# 08_B2B.net
KiCad netlist of a schematic drawn in Altium Designer
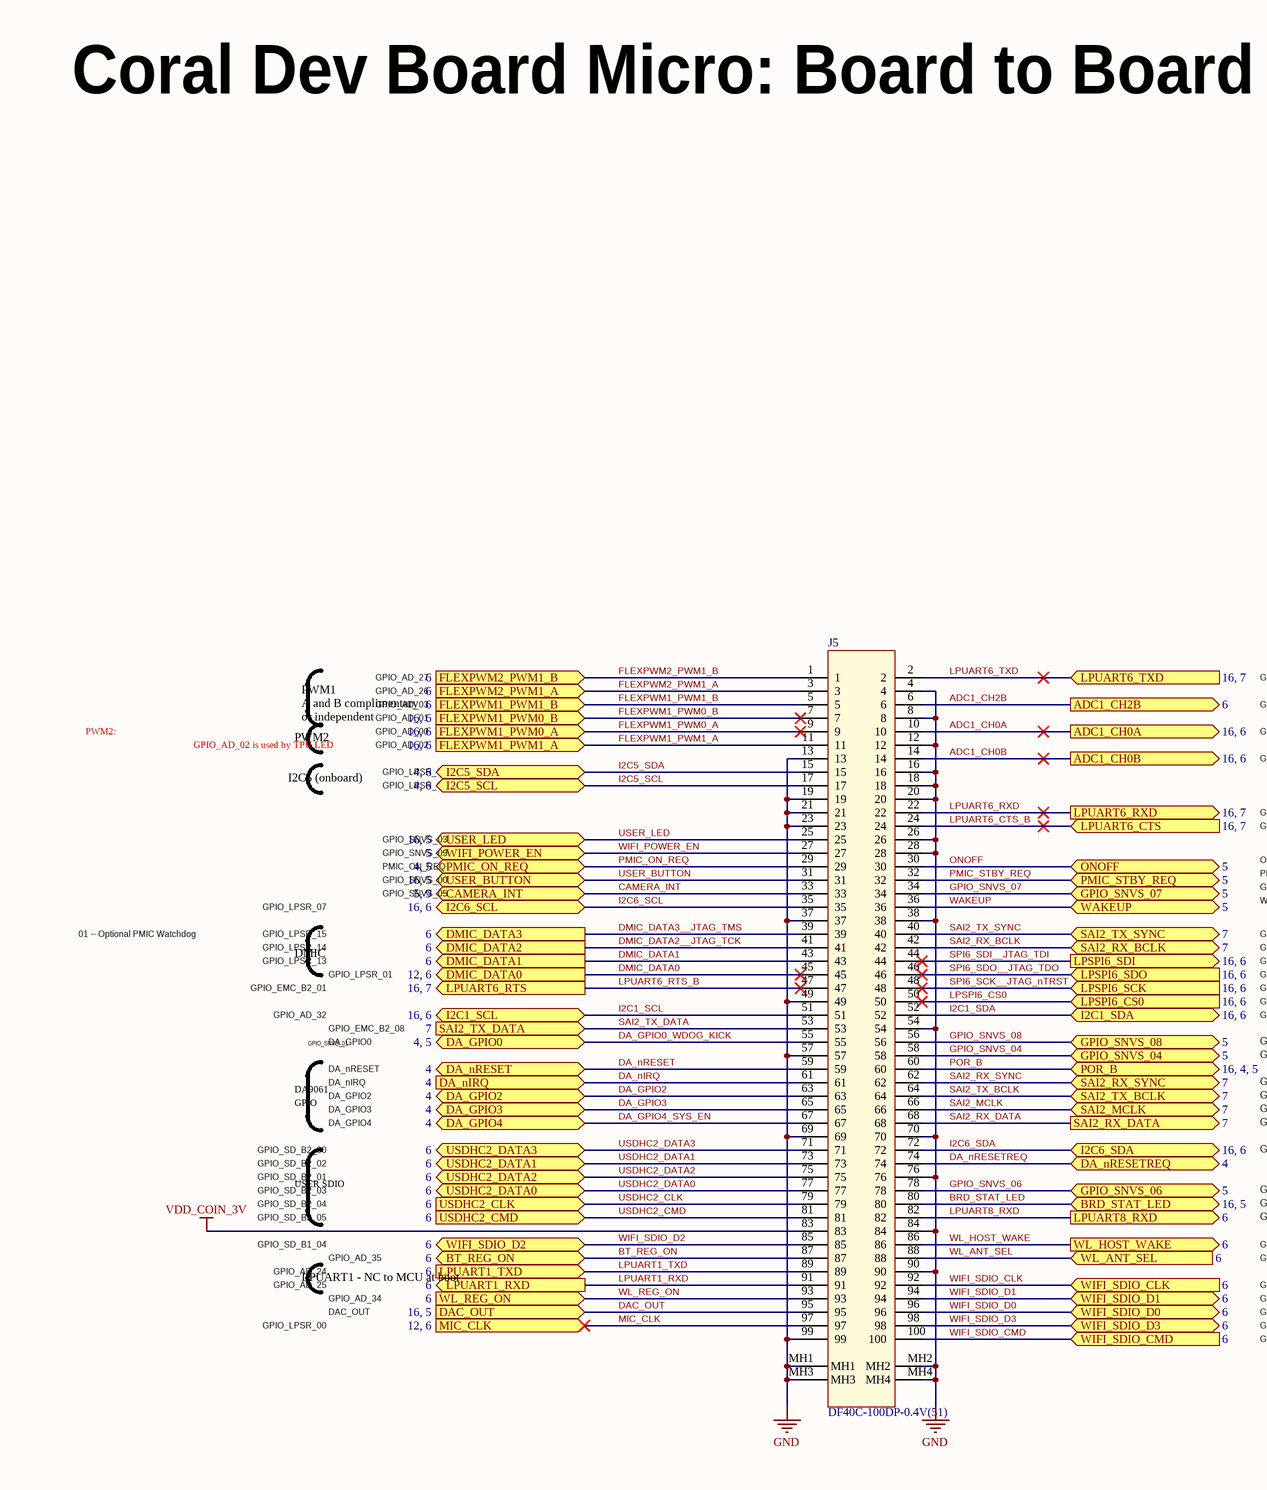
[diagram p0: 08 B2B.SchDoc, left]
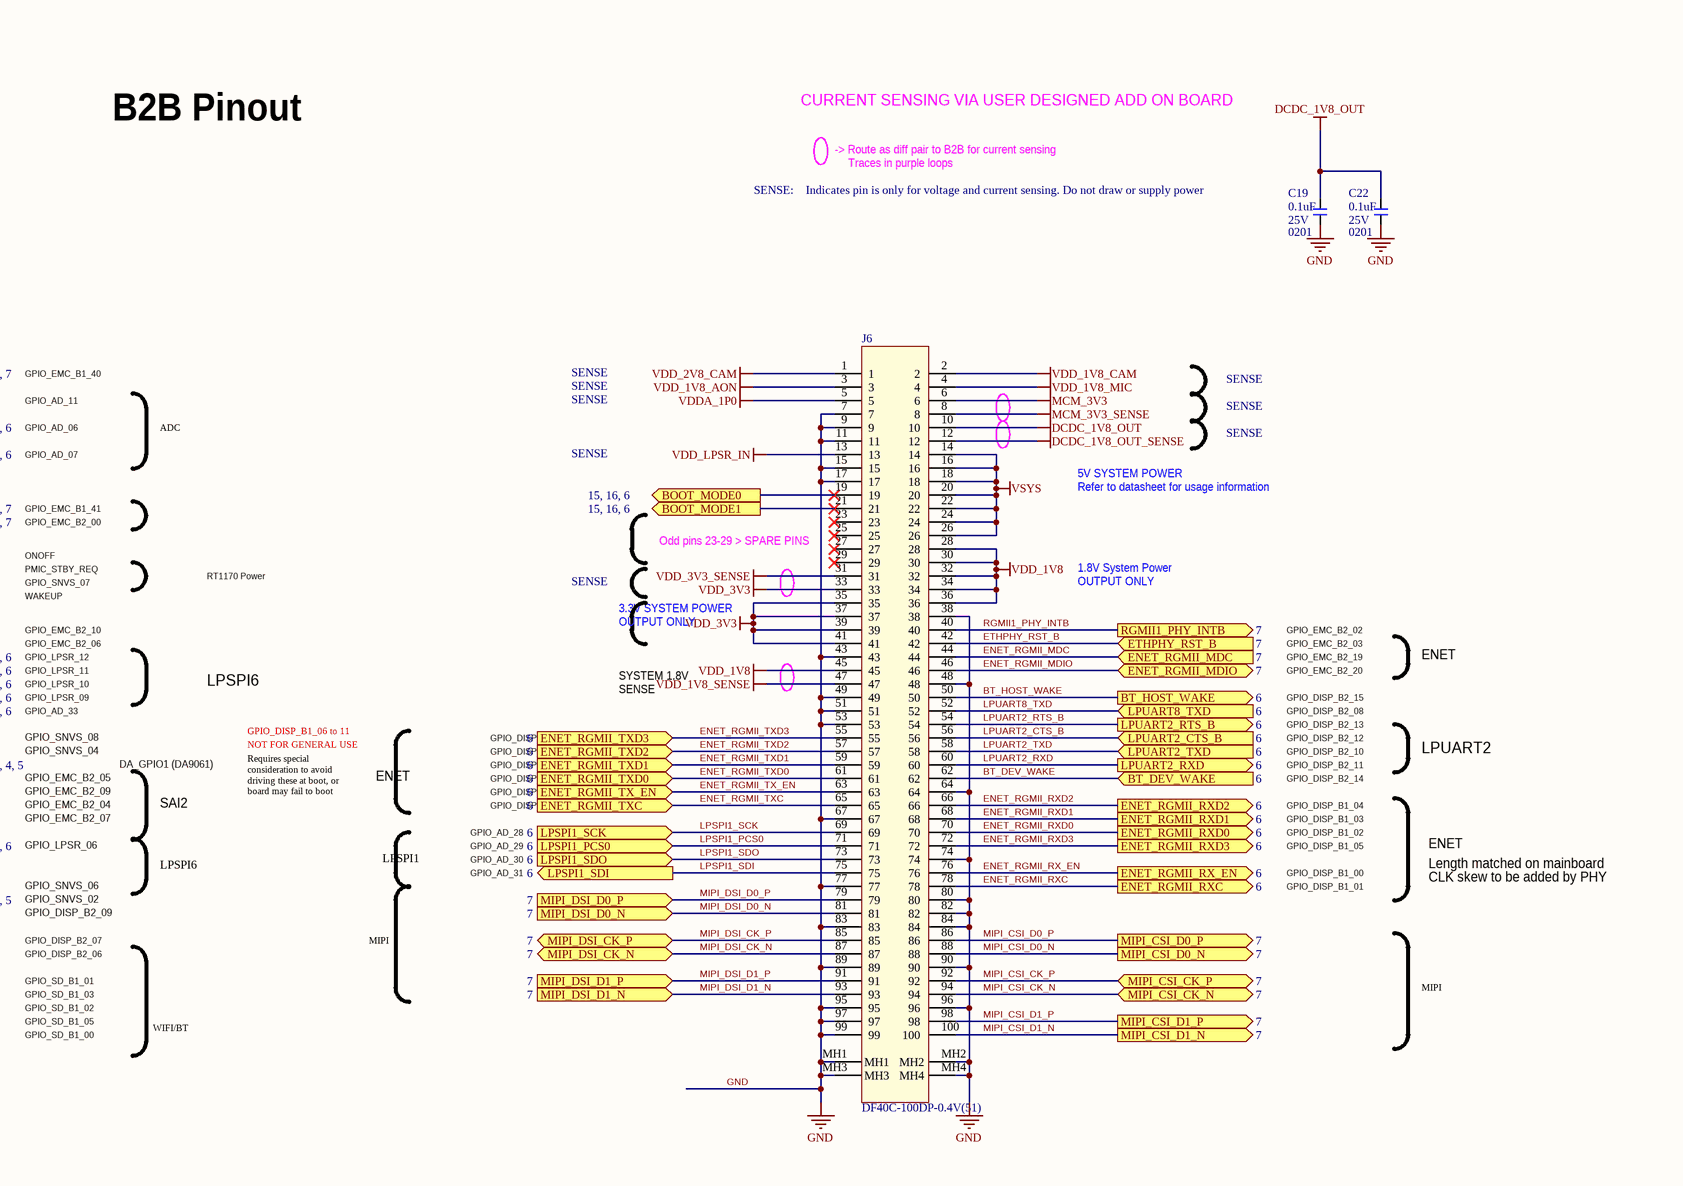
[diagram p1: 08 B2B.SchDoc, right]

(export (version "E")
  (design (tool "Eeschema 10.0.6"))
  (components
    (comp (ref "C19")
      (value "0.1uF")
      (footprint "C0201Y")
      (description "CAP, CER, X5R, 0.1uF, 25V, 20%, 0201, 0.33mm T")
      (fields
        (field (name "MFG") "MURATA")
        (field (name "PACKAGE") "0201")
        (field (name "VOLTAGE") "25V")
        (field (name "TOLERANCE") "20%")
      )
      (libsource (lib "AltiumReleaseLibDB") (part "__Template_Cap"))
    )
    (comp (ref "C22")
      (value "0.1uF")
      (footprint "C0201Y")
      (description "CAP, CER, X5R, 0.1uF, 25V, 20%, 0201, 0.33mm T")
      (fields
        (field (name "MFG") "MURATA")
        (field (name "PACKAGE") "0201")
        (field (name "VOLTAGE") "25V")
        (field (name "TOLERANCE") "20%")
      )
      (libsource (lib "AltiumReleaseLibDB") (part "__Template_Cap"))
    )
    (comp (ref "J5")
      (value "~")
      (footprint "HIROSE_DF40C-100DP-0.4V(51)")
      (description "CONN, HDR, VERT, 2x50, 0.4MM P, 1.14MM H, GOLD, SMD")
      (fields (field (name "MFG") "Hirose Electric Co Ltd") (field (name "MFG P/N") "DF40C-100DP-0.4V(51)"))
      (libsource (lib "AltiumReleaseLibDB") (part "__Template_Connector_2X50_4MH"))
    )
    (comp (ref "J6")
      (value "~")
      (footprint "HIROSE_DF40C-100DP-0.4V(51)")
      (description "CONN, HDR, VERT, 2x50, 0.4MM P, 1.14MM H, GOLD, SMD")
      (fields (field (name "MFG") "Hirose Electric Co Ltd") (field (name "MFG P/N") "DF40C-100DP-0.4V(51)"))
      (libsource (lib "AltiumReleaseLibDB") (part "__Template_Connector_2X50_4MH"))
    )
  )
  (nets
    (net (code "1") (name "/ADC1_CH0A") (class "Default")
      (node (ref "J5") (pin "10") (pinfunction "10_10") (pintype "passive"))
    )
    (net (code "2") (name "/ADC1_CH0B") (class "Default")
      (node (ref "J5") (pin "14") (pinfunction "14_14") (pintype "passive"))
    )
    (net (code "3") (name "/ADC1_CH2B") (class "Default")
      (node (ref "J5") (pin "6") (pinfunction "6_6") (pintype "passive"))
    )
    (net (code "4") (name "/BOOT_MODE0") (class "Default")
      (node (ref "J6") (pin "19") (pinfunction "19_19") (pintype "passive+no_connect"))
    )
    (net (code "5") (name "/BOOT_MODE1") (class "Default")
      (node (ref "J6") (pin "21") (pinfunction "21_21") (pintype "passive+no_connect"))
    )
    (net (code "6") (name "/BRD_STAT_LED") (class "Default")
      (node (ref "J5") (pin "80") (pinfunction "80_80") (pintype "passive"))
    )
    (net (code "7") (name "/BT_DEV_WAKE") (class "Default")
      (node (ref "J6") (pin "62") (pinfunction "62_62") (pintype "passive"))
    )
    (net (code "8") (name "/BT_HOST_WAKE") (class "Default")
      (node (ref "J6") (pin "50") (pinfunction "50_50") (pintype "passive"))
    )
    (net (code "9") (name "/BT_REG_ON") (class "Default")
      (node (ref "J5") (pin "87") (pinfunction "87_87") (pintype "passive"))
    )
    (net (code "10") (name "/CAMERA_INT") (class "Default")
      (node (ref "J5") (pin "33") (pinfunction "33_33") (pintype "passive"))
    )
    (net (code "11") (name "/DAC_OUT") (class "Default")
      (node (ref "J5") (pin "95") (pinfunction "95_95") (pintype "passive"))
    )
    (net (code "12") (name "/DA_GPIO0_WDOG_KICK") (class "Default")
      (node (ref "J5") (pin "55") (pinfunction "55_55") (pintype "passive"))
    )
    (net (code "13") (name "/DA_GPIO2") (class "Default")
      (node (ref "J5") (pin "63") (pinfunction "63_63") (pintype "passive"))
    )
    (net (code "14") (name "/DA_GPIO3") (class "Default")
      (node (ref "J5") (pin "65") (pinfunction "65_65") (pintype "passive"))
    )
    (net (code "15") (name "/DA_GPIO4_SYS_EN") (class "Default")
      (node (ref "J5") (pin "67") (pinfunction "67_67") (pintype "passive"))
    )
    (net (code "16") (name "/DA_nIRQ") (class "Default")
      (node (ref "J5") (pin "61") (pinfunction "61_61") (pintype "passive"))
    )
    (net (code "17") (name "/DA_nRESET") (class "Default")
      (node (ref "J5") (pin "59") (pinfunction "59_59") (pintype "passive"))
    )
    (net (code "18") (name "/DA_nRESETREQ") (class "Default")
      (node (ref "J5") (pin "74") (pinfunction "74_74") (pintype "passive"))
    )
    (net (code "19") (name "/DMIC_DATA0") (class "Default")
      (node (ref "J5") (pin "45") (pinfunction "45_45") (pintype "passive+no_connect"))
    )
    (net (code "20") (name "/DMIC_DATA1") (class "Default")
      (node (ref "J5") (pin "43") (pinfunction "43_43") (pintype "passive"))
    )
    (net (code "21") (name "/DMIC_DATA2__JTAG_TCK") (class "Default")
      (node (ref "J5") (pin "41") (pinfunction "41_41") (pintype "passive"))
    )
    (net (code "22") (name "/DMIC_DATA3__JTAG_TMS") (class "Default")
      (node (ref "J5") (pin "39") (pinfunction "39_39") (pintype "passive"))
    )
    (net (code "23") (name "/ENET_RGMII_MDC") (class "Default")
      (node (ref "J6") (pin "44") (pinfunction "44_44") (pintype "passive"))
    )
    (net (code "24") (name "/ENET_RGMII_MDIO") (class "Default")
      (node (ref "J6") (pin "46") (pinfunction "46_46") (pintype "passive"))
    )
    (net (code "25") (name "/ENET_RGMII_RXC") (class "Default")
      (node (ref "J6") (pin "78") (pinfunction "78_78") (pintype "passive"))
    )
    (net (code "26") (name "/ENET_RGMII_RXD0") (class "Default")
      (node (ref "J6") (pin "70") (pinfunction "70_70") (pintype "passive"))
    )
    (net (code "27") (name "/ENET_RGMII_RXD1") (class "Default")
      (node (ref "J6") (pin "68") (pinfunction "68_68") (pintype "passive"))
    )
    (net (code "28") (name "/ENET_RGMII_RXD2") (class "Default")
      (node (ref "J6") (pin "66") (pinfunction "66_66") (pintype "passive"))
    )
    (net (code "29") (name "/ENET_RGMII_RXD3") (class "Default")
      (node (ref "J6") (pin "72") (pinfunction "72_72") (pintype "passive"))
    )
    (net (code "30") (name "/ENET_RGMII_RX_EN") (class "Default")
      (node (ref "J6") (pin "76") (pinfunction "76_76") (pintype "passive"))
    )
    (net (code "31") (name "/ENET_RGMII_TXC") (class "Default")
      (node (ref "J6") (pin "65") (pinfunction "65_65") (pintype "passive"))
    )
    (net (code "32") (name "/ENET_RGMII_TXD0") (class "Default")
      (node (ref "J6") (pin "61") (pinfunction "61_61") (pintype "passive"))
    )
    (net (code "33") (name "/ENET_RGMII_TXD1") (class "Default")
      (node (ref "J6") (pin "59") (pinfunction "59_59") (pintype "passive"))
    )
    (net (code "34") (name "/ENET_RGMII_TXD2") (class "Default")
      (node (ref "J6") (pin "57") (pinfunction "57_57") (pintype "passive"))
    )
    (net (code "35") (name "/ENET_RGMII_TXD3") (class "Default")
      (node (ref "J6") (pin "55") (pinfunction "55_55") (pintype "passive"))
    )
    (net (code "36") (name "/ENET_RGMII_TX_EN") (class "Default")
      (node (ref "J6") (pin "63") (pinfunction "63_63") (pintype "passive"))
    )
    (net (code "37") (name "/ETHPHY_RST_B") (class "Default")
      (node (ref "J6") (pin "42") (pinfunction "42_42") (pintype "passive"))
    )
    (net (code "38") (name "/FLEXPWM1_PWM0_A") (class "Default")
      (node (ref "J5") (pin "9") (pinfunction "9_9") (pintype "passive+no_connect"))
    )
    (net (code "39") (name "/FLEXPWM1_PWM0_B") (class "Default")
      (node (ref "J5") (pin "7") (pinfunction "7_7") (pintype "passive+no_connect"))
    )
    (net (code "40") (name "/FLEXPWM1_PWM1_A") (class "Default")
      (node (ref "J5") (pin "11") (pinfunction "11_11") (pintype "passive"))
    )
    (net (code "41") (name "/FLEXPWM1_PWM1_B") (class "Default")
      (node (ref "J5") (pin "5") (pinfunction "5_5") (pintype "passive"))
    )
    (net (code "42") (name "/FLEXPWM2_PWM1_A") (class "Default")
      (node (ref "J5") (pin "3") (pinfunction "3_3") (pintype "passive"))
    )
    (net (code "43") (name "/FLEXPWM2_PWM1_B") (class "Default")
      (node (ref "J5") (pin "1") (pinfunction "1_1") (pintype "passive"))
    )
    (net (code "44") (name "/GPIO_SNVS_04") (class "Default")
      (node (ref "J5") (pin "58") (pinfunction "58_58") (pintype "passive"))
    )
    (net (code "45") (name "/GPIO_SNVS_06") (class "Default")
      (node (ref "J5") (pin "78") (pinfunction "78_78") (pintype "passive"))
    )
    (net (code "46") (name "/GPIO_SNVS_07") (class "Default")
      (node (ref "J5") (pin "34") (pinfunction "34_34") (pintype "passive"))
    )
    (net (code "47") (name "/GPIO_SNVS_08") (class "Default")
      (node (ref "J5") (pin "56") (pinfunction "56_56") (pintype "passive"))
    )
    (net (code "48") (name "/I2C1_SCL") (class "Default")
      (node (ref "J5") (pin "51") (pinfunction "51_51") (pintype "passive"))
    )
    (net (code "49") (name "/I2C1_SDA") (class "Default")
      (node (ref "J5") (pin "52") (pinfunction "52_52") (pintype "passive"))
    )
    (net (code "50") (name "/I2C5_SCL") (class "Default")
      (node (ref "J5") (pin "17") (pinfunction "17_17") (pintype "passive"))
    )
    (net (code "51") (name "/I2C5_SDA") (class "Default")
      (node (ref "J5") (pin "15") (pinfunction "15_15") (pintype "passive"))
    )
    (net (code "52") (name "/I2C6_SCL") (class "Default")
      (node (ref "J5") (pin "35") (pinfunction "35_35") (pintype "passive"))
    )
    (net (code "53") (name "/I2C6_SDA") (class "Default")
      (node (ref "J5") (pin "72") (pinfunction "72_72") (pintype "passive"))
    )
    (net (code "54") (name "/LPSPI1_PCS0") (class "Default")
      (node (ref "J6") (pin "71") (pinfunction "71_71") (pintype "passive"))
    )
    (net (code "55") (name "/LPSPI1_SCK") (class "Default")
      (node (ref "J6") (pin "69") (pinfunction "69_69") (pintype "passive"))
    )
    (net (code "56") (name "/LPSPI1_SDI") (class "Default")
      (node (ref "J6") (pin "75") (pinfunction "75_75") (pintype "passive"))
    )
    (net (code "57") (name "/LPSPI1_SDO") (class "Default")
      (node (ref "J6") (pin "73") (pinfunction "73_73") (pintype "passive"))
    )
    (net (code "58") (name "/LPSPI6_CS0") (class "Default")
      (node (ref "J5") (pin "50") (pinfunction "50_50") (pintype "passive+no_connect"))
    )
    (net (code "59") (name "/LPUART1_RXD") (class "Default")
      (node (ref "J5") (pin "91") (pinfunction "91_91") (pintype "passive"))
    )
    (net (code "60") (name "/LPUART1_TXD") (class "Default")
      (node (ref "J5") (pin "89") (pinfunction "89_89") (pintype "passive"))
    )
    (net (code "61") (name "/LPUART2_CTS_B") (class "Default")
      (node (ref "J6") (pin "56") (pinfunction "56_56") (pintype "passive"))
    )
    (net (code "62") (name "/LPUART2_RTS_B") (class "Default")
      (node (ref "J6") (pin "54") (pinfunction "54_54") (pintype "passive"))
    )
    (net (code "63") (name "/LPUART2_RXD") (class "Default")
      (node (ref "J6") (pin "60") (pinfunction "60_60") (pintype "passive"))
    )
    (net (code "64") (name "/LPUART2_TXD") (class "Default")
      (node (ref "J6") (pin "58") (pinfunction "58_58") (pintype "passive"))
    )
    (net (code "65") (name "/LPUART6_CTS_B") (class "Default")
      (node (ref "J5") (pin "24") (pinfunction "24_24") (pintype "passive"))
    )
    (net (code "66") (name "/LPUART6_RTS_B") (class "Default")
      (node (ref "J5") (pin "47") (pinfunction "47_47") (pintype "passive+no_connect"))
    )
    (net (code "67") (name "/LPUART6_RXD") (class "Default")
      (node (ref "J5") (pin "22") (pinfunction "22_22") (pintype "passive"))
    )
    (net (code "68") (name "/LPUART6_TXD") (class "Default")
      (node (ref "J5") (pin "2") (pinfunction "2_2") (pintype "passive"))
    )
    (net (code "69") (name "/LPUART8_RXD") (class "Default")
      (node (ref "J5") (pin "82") (pinfunction "82_82") (pintype "passive"))
    )
    (net (code "70") (name "/LPUART8_TXD") (class "Default")
      (node (ref "J6") (pin "52") (pinfunction "52_52") (pintype "passive"))
    )
    (net (code "71") (name "/MIC_CLK") (class "Default")
      (node (ref "J5") (pin "97") (pinfunction "97_97") (pintype "passive+no_connect"))
    )
    (net (code "72") (name "/MIPI_CSI_CK_N") (class "Default")
      (node (ref "J6") (pin "94") (pinfunction "94_94") (pintype "passive"))
    )
    (net (code "73") (name "/MIPI_CSI_CK_P") (class "Default")
      (node (ref "J6") (pin "92") (pinfunction "92_92") (pintype "passive"))
    )
    (net (code "74") (name "/MIPI_CSI_D0_N") (class "Default")
      (node (ref "J6") (pin "88") (pinfunction "88_88") (pintype "passive"))
    )
    (net (code "75") (name "/MIPI_CSI_D0_P") (class "Default")
      (node (ref "J6") (pin "86") (pinfunction "86_86") (pintype "passive"))
    )
    (net (code "76") (name "/MIPI_CSI_D1_N") (class "Default")
      (node (ref "J6") (pin "100") (pinfunction "100_100") (pintype "passive"))
    )
    (net (code "77") (name "/MIPI_CSI_D1_P") (class "Default")
      (node (ref "J6") (pin "98") (pinfunction "98_98") (pintype "passive"))
    )
    (net (code "78") (name "/MIPI_DSI_CK_N") (class "Default")
      (node (ref "J6") (pin "87") (pinfunction "87_87") (pintype "passive"))
    )
    (net (code "79") (name "/MIPI_DSI_CK_P") (class "Default")
      (node (ref "J6") (pin "85") (pinfunction "85_85") (pintype "passive"))
    )
    (net (code "80") (name "/MIPI_DSI_D0_N") (class "Default")
      (node (ref "J6") (pin "81") (pinfunction "81_81") (pintype "passive"))
    )
    (net (code "81") (name "/MIPI_DSI_D0_P") (class "Default")
      (node (ref "J6") (pin "79") (pinfunction "79_79") (pintype "passive"))
    )
    (net (code "82") (name "/MIPI_DSI_D1_N") (class "Default")
      (node (ref "J6") (pin "93") (pinfunction "93_93") (pintype "passive"))
    )
    (net (code "83") (name "/MIPI_DSI_D1_P") (class "Default")
      (node (ref "J6") (pin "91") (pinfunction "91_91") (pintype "passive"))
    )
    (net (code "84") (name "/ONOFF") (class "Default")
      (node (ref "J5") (pin "30") (pinfunction "30_30") (pintype "passive"))
    )
    (net (code "85") (name "/PMIC_ON_REQ") (class "Default")
      (node (ref "J5") (pin "29") (pinfunction "29_29") (pintype "passive"))
    )
    (net (code "86") (name "/PMIC_STBY_REQ") (class "Default")
      (node (ref "J5") (pin "32") (pinfunction "32_32") (pintype "passive"))
    )
    (net (code "87") (name "/POR_B") (class "Default")
      (node (ref "J5") (pin "60") (pinfunction "60_60") (pintype "passive"))
    )
    (net (code "88") (name "/RGMII1_PHY_INTB") (class "Default")
      (node (ref "J6") (pin "40") (pinfunction "40_40") (pintype "passive"))
    )
    (net (code "89") (name "/SAI2_MCLK") (class "Default")
      (node (ref "J5") (pin "66") (pinfunction "66_66") (pintype "passive"))
    )
    (net (code "90") (name "/SAI2_RX_BCLK") (class "Default")
      (node (ref "J5") (pin "42") (pinfunction "42_42") (pintype "passive"))
    )
    (net (code "91") (name "/SAI2_RX_DATA") (class "Default")
      (node (ref "J5") (pin "68") (pinfunction "68_68") (pintype "passive"))
    )
    (net (code "92") (name "/SAI2_RX_SYNC") (class "Default")
      (node (ref "J5") (pin "62") (pinfunction "62_62") (pintype "passive"))
    )
    (net (code "93") (name "/SAI2_TX_BCLK") (class "Default")
      (node (ref "J5") (pin "64") (pinfunction "64_64") (pintype "passive"))
    )
    (net (code "94") (name "/SAI2_TX_DATA") (class "Default")
      (node (ref "J5") (pin "53") (pinfunction "53_53") (pintype "passive"))
    )
    (net (code "95") (name "/SAI2_TX_SYNC") (class "Default")
      (node (ref "J5") (pin "40") (pinfunction "40_40") (pintype "passive"))
    )
    (net (code "96") (name "/SPI6_SCK__JTAG_nTRST") (class "Default")
      (node (ref "J5") (pin "48") (pinfunction "48_48") (pintype "passive+no_connect"))
    )
    (net (code "97") (name "/SPI6_SDI__JTAG_TDI") (class "Default")
      (node (ref "J5") (pin "44") (pinfunction "44_44") (pintype "passive+no_connect"))
    )
    (net (code "98") (name "/SPI6_SDO__JTAG_TDO") (class "Default")
      (node (ref "J5") (pin "46") (pinfunction "46_46") (pintype "passive+no_connect"))
    )
    (net (code "99") (name "/USDHC2_CLK") (class "Default")
      (node (ref "J5") (pin "79") (pinfunction "79_79") (pintype "passive"))
    )
    (net (code "100") (name "/USDHC2_CMD") (class "Default")
      (node (ref "J5") (pin "81") (pinfunction "81_81") (pintype "passive"))
    )
    (net (code "101") (name "/USDHC2_DATA0") (class "Default")
      (node (ref "J5") (pin "77") (pinfunction "77_77") (pintype "passive"))
    )
    (net (code "102") (name "/USDHC2_DATA1") (class "Default")
      (node (ref "J5") (pin "73") (pinfunction "73_73") (pintype "passive"))
    )
    (net (code "103") (name "/USDHC2_DATA2") (class "Default")
      (node (ref "J5") (pin "75") (pinfunction "75_75") (pintype "passive"))
    )
    (net (code "104") (name "/USDHC2_DATA3") (class "Default")
      (node (ref "J5") (pin "71") (pinfunction "71_71") (pintype "passive"))
    )
    (net (code "105") (name "/USER_BUTTON") (class "Default")
      (node (ref "J5") (pin "31") (pinfunction "31_31") (pintype "passive"))
    )
    (net (code "106") (name "/USER_LED") (class "Default")
      (node (ref "J5") (pin "25") (pinfunction "25_25") (pintype "passive"))
    )
    (net (code "107") (name "/WAKEUP") (class "Default")
      (node (ref "J5") (pin "36") (pinfunction "36_36") (pintype "passive"))
    )
    (net (code "108") (name "/WIFI_POWER_EN") (class "Default")
      (node (ref "J5") (pin "27") (pinfunction "27_27") (pintype "passive"))
    )
    (net (code "109") (name "/WIFI_SDIO_CLK") (class "Default")
      (node (ref "J5") (pin "92") (pinfunction "92_92") (pintype "passive"))
    )
    (net (code "110") (name "/WIFI_SDIO_CMD") (class "Default")
      (node (ref "J5") (pin "100") (pinfunction "100_100") (pintype "passive"))
    )
    (net (code "111") (name "/WIFI_SDIO_D0") (class "Default")
      (node (ref "J5") (pin "96") (pinfunction "96_96") (pintype "passive"))
    )
    (net (code "112") (name "/WIFI_SDIO_D1") (class "Default")
      (node (ref "J5") (pin "94") (pinfunction "94_94") (pintype "passive"))
    )
    (net (code "113") (name "/WIFI_SDIO_D2") (class "Default")
      (node (ref "J5") (pin "85") (pinfunction "85_85") (pintype "passive"))
    )
    (net (code "114") (name "/WIFI_SDIO_D3") (class "Default")
      (node (ref "J5") (pin "98") (pinfunction "98_98") (pintype "passive"))
    )
    (net (code "115") (name "/WL_ANT_SEL") (class "Default")
      (node (ref "J5") (pin "88") (pinfunction "88_88") (pintype "passive"))
    )
    (net (code "116") (name "/WL_HOST_WAKE") (class "Default")
      (node (ref "J5") (pin "86") (pinfunction "86_86") (pintype "passive"))
    )
    (net (code "117") (name "/WL_REG_ON") (class "Default")
      (node (ref "J5") (pin "93") (pinfunction "93_93") (pintype "passive"))
    )
    (net (code "118") (name "DCDC_1V8_OUT") (class "Default")
      (node (ref "C19") (pin "1") (pintype "passive"))
      (node (ref "C22") (pin "1") (pintype "passive"))
      (node (ref "J6") (pin "10") (pinfunction "10_10") (pintype "passive"))
    )
    (net (code "119") (name "DCDC_1V8_OUT_SENSE") (class "Default")
      (node (ref "J6") (pin "12") (pinfunction "12_12") (pintype "passive"))
    )
    (net (code "120") (name "GND") (class "Default")
      (node (ref "C19") (pin "2") (pintype "passive"))
      (node (ref "C22") (pin "2") (pintype "passive"))
      (node (ref "J5") (pin "12") (pinfunction "12_12") (pintype "passive"))
      (node (ref "J5") (pin "13") (pinfunction "13_13") (pintype "passive"))
      (node (ref "J5") (pin "16") (pinfunction "16_16") (pintype "passive"))
      (node (ref "J5") (pin "18") (pinfunction "18_18") (pintype "passive"))
      (node (ref "J5") (pin "19") (pinfunction "19_19") (pintype "passive"))
      (node (ref "J5") (pin "20") (pinfunction "20_20") (pintype "passive"))
      (node (ref "J5") (pin "21") (pinfunction "21_21") (pintype "passive"))
      (node (ref "J5") (pin "23") (pinfunction "23_23") (pintype "passive"))
      (node (ref "J5") (pin "26") (pinfunction "26_26") (pintype "passive"))
      (node (ref "J5") (pin "28") (pinfunction "28_28") (pintype "passive"))
      (node (ref "J5") (pin "37") (pinfunction "37_37") (pintype "passive"))
      (node (ref "J5") (pin "38") (pinfunction "38_38") (pintype "passive"))
      (node (ref "J5") (pin "4") (pinfunction "4_4") (pintype "passive"))
      (node (ref "J5") (pin "49") (pinfunction "49_49") (pintype "passive"))
      (node (ref "J5") (pin "54") (pinfunction "54_54") (pintype "passive"))
      (node (ref "J5") (pin "57") (pinfunction "57_57") (pintype "passive"))
      (node (ref "J5") (pin "69") (pinfunction "69_69") (pintype "passive"))
      (node (ref "J5") (pin "70") (pinfunction "70_70") (pintype "passive"))
      (node (ref "J5") (pin "76") (pinfunction "76_76") (pintype "passive"))
      (node (ref "J5") (pin "8") (pinfunction "8_8") (pintype "passive"))
      (node (ref "J5") (pin "84") (pinfunction "84_84") (pintype "passive"))
      (node (ref "J5") (pin "90") (pinfunction "90_90") (pintype "passive"))
      (node (ref "J5") (pin "99") (pinfunction "99_99") (pintype "passive"))
      (node (ref "J5") (pin "MH1") (pinfunction "MH1_MH1") (pintype "passive"))
      (node (ref "J5") (pin "MH2") (pinfunction "MH2_MH2") (pintype "passive"))
      (node (ref "J5") (pin "MH3") (pinfunction "MH3_MH3") (pintype "passive"))
      (node (ref "J5") (pin "MH4") (pinfunction "MH4_MH4") (pintype "passive"))
      (node (ref "J6") (pin "11") (pinfunction "11_11") (pintype "passive"))
      (node (ref "J6") (pin "15") (pinfunction "15_15") (pintype "passive"))
      (node (ref "J6") (pin "17") (pinfunction "17_17") (pintype "passive"))
      (node (ref "J6") (pin "38") (pinfunction "38_38") (pintype "passive"))
      (node (ref "J6") (pin "43") (pinfunction "43_43") (pintype "passive"))
      (node (ref "J6") (pin "48") (pinfunction "48_48") (pintype "passive"))
      (node (ref "J6") (pin "49") (pinfunction "49_49") (pintype "passive"))
      (node (ref "J6") (pin "51") (pinfunction "51_51") (pintype "passive"))
      (node (ref "J6") (pin "53") (pinfunction "53_53") (pintype "passive"))
      (node (ref "J6") (pin "64") (pinfunction "64_64") (pintype "passive"))
      (node (ref "J6") (pin "67") (pinfunction "67_67") (pintype "passive"))
      (node (ref "J6") (pin "7") (pinfunction "7_7") (pintype "passive"))
      (node (ref "J6") (pin "74") (pinfunction "74_74") (pintype "passive"))
      (node (ref "J6") (pin "77") (pinfunction "77_77") (pintype "passive"))
      (node (ref "J6") (pin "80") (pinfunction "80_80") (pintype "passive"))
      (node (ref "J6") (pin "82") (pinfunction "82_82") (pintype "passive"))
      (node (ref "J6") (pin "83") (pinfunction "83_83") (pintype "passive"))
      (node (ref "J6") (pin "84") (pinfunction "84_84") (pintype "passive"))
      (node (ref "J6") (pin "89") (pinfunction "89_89") (pintype "passive"))
      (node (ref "J6") (pin "9") (pinfunction "9_9") (pintype "passive"))
      (node (ref "J6") (pin "90") (pinfunction "90_90") (pintype "passive"))
      (node (ref "J6") (pin "95") (pinfunction "95_95") (pintype "passive"))
      (node (ref "J6") (pin "96") (pinfunction "96_96") (pintype "passive"))
      (node (ref "J6") (pin "97") (pinfunction "97_97") (pintype "passive"))
      (node (ref "J6") (pin "99") (pinfunction "99_99") (pintype "passive"))
      (node (ref "J6") (pin "MH1") (pinfunction "MH1_MH1") (pintype "passive"))
      (node (ref "J6") (pin "MH2") (pinfunction "MH2_MH2") (pintype "passive"))
      (node (ref "J6") (pin "MH3") (pinfunction "MH3_MH3") (pintype "passive"))
      (node (ref "J6") (pin "MH4") (pinfunction "MH4_MH4") (pintype "passive"))
    )
    (net (code "121") (name "MCM_3V3") (class "Default")
      (node (ref "J6") (pin "6") (pinfunction "6_6") (pintype "passive"))
    )
    (net (code "122") (name "MCM_3V3_SENSE") (class "Default")
      (node (ref "J6") (pin "8") (pinfunction "8_8") (pintype "passive"))
    )
    (net (code "123") (name "VDDA_1P0") (class "Default")
      (node (ref "J6") (pin "5") (pinfunction "5_5") (pintype "passive"))
    )
    (net (code "124") (name "VDD_1V8") (class "Default")
      (node (ref "J6") (pin "28") (pinfunction "28_28") (pintype "passive"))
      (node (ref "J6") (pin "30") (pinfunction "30_30") (pintype "passive"))
      (node (ref "J6") (pin "32") (pinfunction "32_32") (pintype "passive"))
      (node (ref "J6") (pin "34") (pinfunction "34_34") (pintype "passive"))
      (node (ref "J6") (pin "36") (pinfunction "36_36") (pintype "passive"))
      (node (ref "J6") (pin "45") (pinfunction "45_45") (pintype "passive"))
    )
    (net (code "125") (name "VDD_1V8_AON") (class "Default")
      (node (ref "J6") (pin "3") (pinfunction "3_3") (pintype "passive"))
    )
    (net (code "126") (name "VDD_1V8_CAM") (class "Default")
      (node (ref "J6") (pin "2") (pinfunction "2_2") (pintype "passive"))
    )
    (net (code "127") (name "VDD_1V8_MIC") (class "Default")
      (node (ref "J6") (pin "4") (pinfunction "4_4") (pintype "passive"))
    )
    (net (code "128") (name "VDD_1V8_SENSE") (class "Default")
      (node (ref "J6") (pin "47") (pinfunction "47_47") (pintype "passive"))
    )
    (net (code "129") (name "VDD_2V8_CAM") (class "Default")
      (node (ref "J6") (pin "1") (pinfunction "1_1") (pintype "passive"))
    )
    (net (code "130") (name "VDD_3V3") (class "Default")
      (node (ref "J6") (pin "33") (pinfunction "33_33") (pintype "passive"))
      (node (ref "J6") (pin "35") (pinfunction "35_35") (pintype "passive"))
      (node (ref "J6") (pin "37") (pinfunction "37_37") (pintype "passive"))
      (node (ref "J6") (pin "39") (pinfunction "39_39") (pintype "passive"))
      (node (ref "J6") (pin "41") (pinfunction "41_41") (pintype "passive"))
    )
    (net (code "131") (name "VDD_3V3_SENSE") (class "Default")
      (node (ref "J6") (pin "31") (pinfunction "31_31") (pintype "passive"))
    )
    (net (code "132") (name "VDD_COIN_3V") (class "Default")
      (node (ref "J5") (pin "83") (pinfunction "83_83") (pintype "passive"))
    )
    (net (code "133") (name "VDD_LPSR_IN") (class "Default")
      (node (ref "J6") (pin "13") (pinfunction "13_13") (pintype "passive"))
    )
    (net (code "134") (name "VSYS") (class "Default")
      (node (ref "J6") (pin "14") (pinfunction "14_14") (pintype "passive"))
      (node (ref "J6") (pin "16") (pinfunction "16_16") (pintype "passive"))
      (node (ref "J6") (pin "18") (pinfunction "18_18") (pintype "passive"))
      (node (ref "J6") (pin "20") (pinfunction "20_20") (pintype "passive"))
      (node (ref "J6") (pin "22") (pinfunction "22_22") (pintype "passive"))
      (node (ref "J6") (pin "24") (pinfunction "24_24") (pintype "passive"))
      (node (ref "J6") (pin "26") (pinfunction "26_26") (pintype "passive"))
    )
    (net (code "135") (name "unconnected-(J6-Pad23)") (class "Default")
      (node (ref "J6") (pin "23") (pinfunction "23_23") (pintype "passive+no_connect"))
    )
    (net (code "136") (name "unconnected-(J6-Pad25)") (class "Default")
      (node (ref "J6") (pin "25") (pinfunction "25_25") (pintype "passive+no_connect"))
    )
    (net (code "137") (name "unconnected-(J6-Pad27)") (class "Default")
      (node (ref "J6") (pin "27") (pinfunction "27_27") (pintype "passive+no_connect"))
    )
    (net (code "138") (name "unconnected-(J6-Pad29)") (class "Default")
      (node (ref "J6") (pin "29") (pinfunction "29_29") (pintype "passive+no_connect"))
    )
  )
)
